# 1.net
KiCad netlist of a schematic drawn in Altium Designer
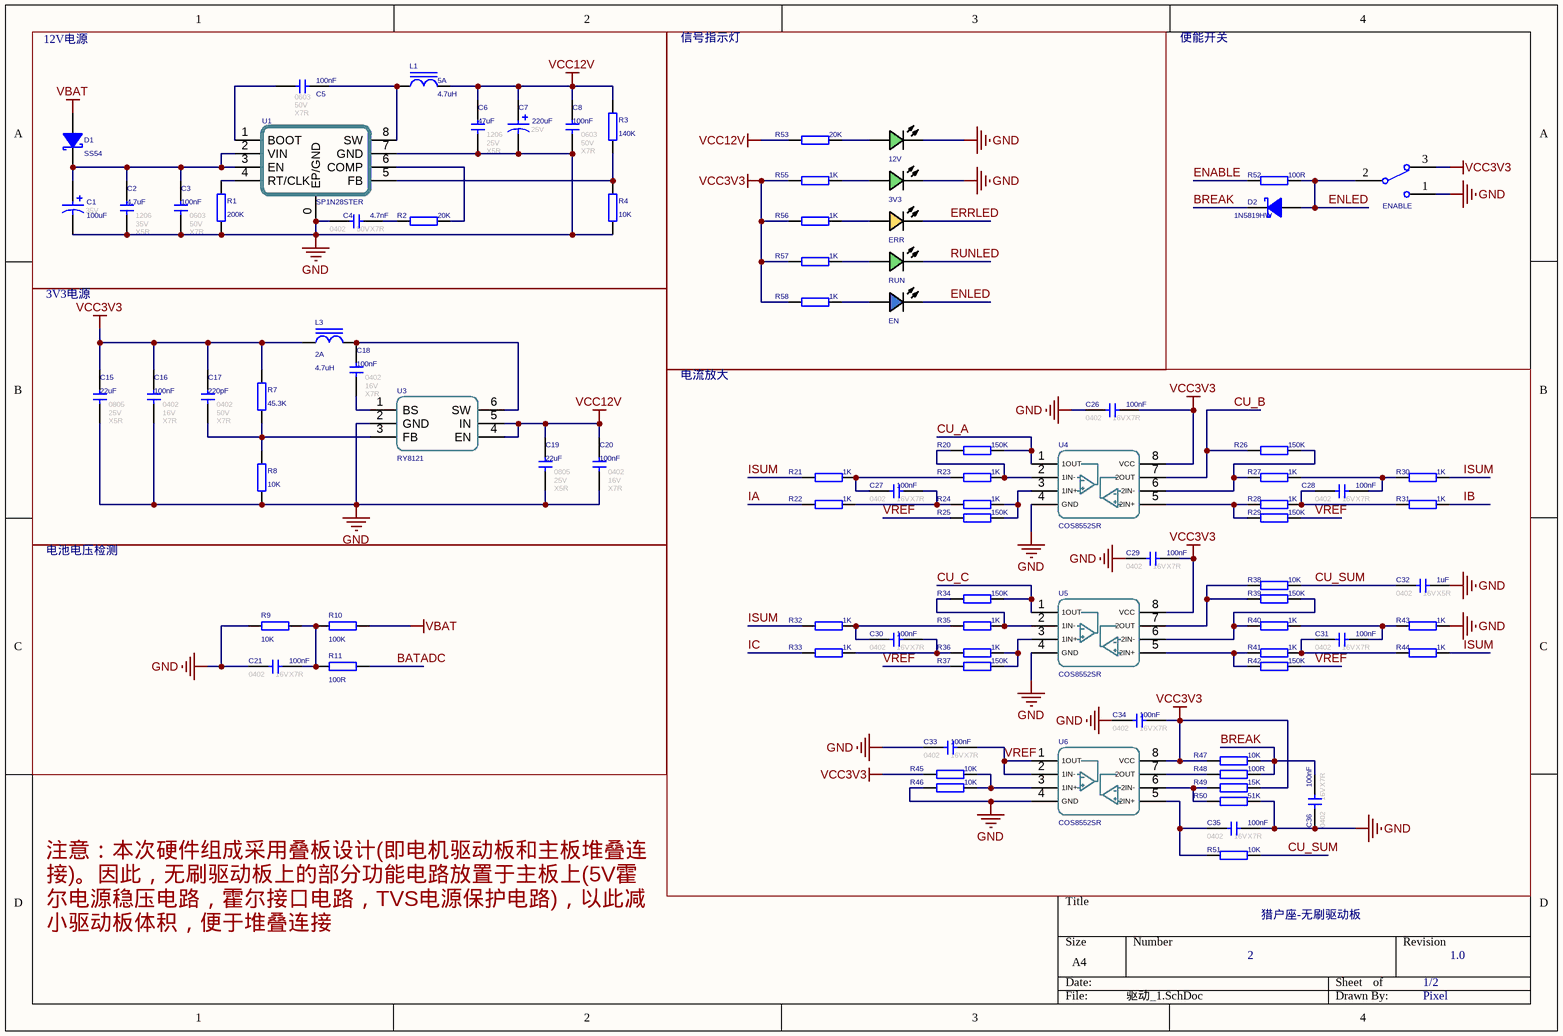
[diagram p0: 驱动_1.SchDoc]

(export (version "E")
  (design (tool "Eeschema 10.0.6"))
  (components
    (comp (ref "3V3")
      (value "翠绿贴片LED")
      (footprint "LEDC1608(0603)-L")
      (fields (field (name "PUBLISHER") "Altium Limited"))
      (libsource (lib "无刷驱动-Infineon-AUIRS2181S-GTM-6S") (part "LED Chip Green"))
    )
    (comp (ref "12V")
      (value "翠绿贴片LED")
      (footprint "LEDC1608(0603)-L")
      (fields (field (name "PUBLISHER") "Altium Limited"))
      (libsource (lib "无刷驱动-Infineon-AUIRS2181S-GTM-6S") (part "LED Chip Green"))
    )
    (comp (ref "C1")
      (value "100uF")
      (footprint "CAP-E-S 6.3")
      (description "贴片电解电容 100uF 35V 6.3x7.7")
      (fields (field (name "VOLTAGE") "35V") (field (name "Comment") "100uF 35V 铝电解"))
      (libsource (lib "无刷驱动-Infineon-AUIRS2181S-GTM-6S") (part "E-S 100uF 35V 6.3x7.7"))
    )
    (comp (ref "C2")
      (value "4.7uF")
      (footprint "1206")
      (description "贴片瓷片电容; MLCC; 1206(3216);")
      (fields
        (field (name "VOLTAGE") "35V")
        (field (name "TYPE") "X5R")
        (field (name "Comment") "4.7uF 35V X5R")
      )
      (libsource (lib "无刷驱动-Infineon-AUIRS2181S-GTM-6S") (part "4.7uF 1206 35V X5R"))
    )
    (comp (ref "C3")
      (value "100nF")
      (footprint "0603")
      (description "贴片瓷片电容; MLCC; 0603(1608);")
      (fields
        (field (name "VOLTAGE") "50V")
        (field (name "TYPE") "X7R")
        (field (name "Comment") "100nF 50V X7R")
      )
      (libsource (lib "无刷驱动-Infineon-AUIRS2181S-GTM-6S") (part "100nF 0603 50V X7R"))
    )
    (comp (ref "C4")
      (value "4.7nF")
      (footprint "0402")
      (description "贴片瓷片电容; MLCC; 0402(1005);")
      (fields
        (field (name "VOLTAGE") "50V")
        (field (name "TYPE") "X7R")
        (field (name "Comment") "4.7nF 50V X7R")
      )
      (libsource (lib "无刷驱动-Infineon-AUIRS2181S-GTM-6S") (part "4.7nF 0402 50V X7R"))
    )
    (comp (ref "C5")
      (value "100nF")
      (footprint "0603")
      (description "贴片瓷片电容; MLCC; 0603(1608);")
      (fields
        (field (name "VOLTAGE") "50V")
        (field (name "TYPE") "X7R")
        (field (name "Comment") "100nF 50V X7R")
      )
      (libsource (lib "无刷驱动-Infineon-AUIRS2181S-GTM-6S") (part "100nF 0603 50V X7R"))
    )
    (comp (ref "C6")
      (value "47uF")
      (footprint "1206")
      (description "贴片瓷片电容; MLCC; 1206(3216);")
      (fields
        (field (name "VOLTAGE") "25V")
        (field (name "TYPE") "X5R")
        (field (name "Comment") "47uF 25V X5R")
      )
      (libsource (lib "无刷驱动-Infineon-AUIRS2181S-GTM-6S") (part "47uF 1206 25V X5R"))
    )
    (comp (ref "C7")
      (value "220uF")
      (footprint "CAP-E-S 6.3")
      (description "贴片电解电容 220uF 25V 6.3x7.7")
      (fields (field (name "VOLTAGE") "25V") (field (name "Comment") "220uF 25V 铝电解"))
      (libsource (lib "无刷驱动-Infineon-AUIRS2181S-GTM-6S") (part "E-S 220uF 25V 6.3x7.7"))
    )
    (comp (ref "C8")
      (value "100nF")
      (footprint "0603")
      (description "贴片瓷片电容; MLCC; 0603(1608);")
      (fields
        (field (name "VOLTAGE") "50V")
        (field (name "TYPE") "X7R")
        (field (name "Comment") "100nF 50V X7R")
      )
      (libsource (lib "无刷驱动-Infineon-AUIRS2181S-GTM-6S") (part "100nF 0603 50V X7R"))
    )
    (comp (ref "C15")
      (value "22uF")
      (footprint "0805")
      (description "贴片瓷片电容; MLCC; 0805(2012);")
      (fields
        (field (name "VOLTAGE") "25V")
        (field (name "TYPE") "X5R")
        (field (name "Comment") "22uF 25V X5R")
      )
      (libsource (lib "无刷驱动-Infineon-AUIRS2181S-GTM-6S") (part "22uF 0805 25V X5R"))
    )
    (comp (ref "C16")
      (value "100nF")
      (footprint "0402")
      (description "贴片瓷片电容; MLCC; 0402(1005);")
      (fields
        (field (name "VOLTAGE") "16V")
        (field (name "TYPE") "X7R")
        (field (name "Comment") "100nF 16V X7R")
      )
      (libsource (lib "无刷驱动-Infineon-AUIRS2181S-GTM-6S") (part "100nF 0402 16V X7R"))
    )
    (comp (ref "C17")
      (value "220pF")
      (footprint "0402")
      (description "贴片瓷片电容; MLCC; 0402(1005);")
      (fields
        (field (name "VOLTAGE") "50V")
        (field (name "TYPE") "X7R")
        (field (name "Comment") "220pF 50V X7R")
      )
      (libsource (lib "无刷驱动-Infineon-AUIRS2181S-GTM-6S") (part "220pF 0402 50V X7R"))
    )
    (comp (ref "C18")
      (value "100nF")
      (footprint "0402")
      (description "贴片瓷片电容; MLCC; 0402(1005);")
      (fields
        (field (name "VOLTAGE") "16V")
        (field (name "TYPE") "X7R")
        (field (name "Comment") "100nF 16V X7R")
      )
      (libsource (lib "无刷驱动-Infineon-AUIRS2181S-GTM-6S") (part "100nF 0402 16V X7R"))
    )
    (comp (ref "C19")
      (value "22uF")
      (footprint "0805")
      (description "贴片瓷片电容; MLCC; 0805(2012);")
      (fields
        (field (name "VOLTAGE") "25V")
        (field (name "TYPE") "X5R")
        (field (name "Comment") "22uF 25V X5R")
      )
      (libsource (lib "无刷驱动-Infineon-AUIRS2181S-GTM-6S") (part "22uF 0805 25V X5R"))
    )
    (comp (ref "C20")
      (value "100nF")
      (footprint "0402")
      (description "贴片瓷片电容; MLCC; 0402(1005);")
      (fields
        (field (name "VOLTAGE") "16V")
        (field (name "TYPE") "X7R")
        (field (name "Comment") "100nF 16V X7R")
      )
      (libsource (lib "无刷驱动-Infineon-AUIRS2181S-GTM-6S") (part "100nF 0402 16V X7R"))
    )
    (comp (ref "C21")
      (value "100nF")
      (footprint "0402")
      (description "贴片瓷片电容; MLCC; 0402(1005);")
      (fields
        (field (name "VOLTAGE") "16V")
        (field (name "TYPE") "X7R")
        (field (name "Comment") "100nF 16V X7R")
      )
      (libsource (lib "无刷驱动-Infineon-AUIRS2181S-GTM-6S") (part "100nF 0402 16V X7R"))
    )
    (comp (ref "C26")
      (value "100nF")
      (footprint "0402")
      (description "贴片瓷片电容; MLCC; 0402(1005);")
      (fields
        (field (name "VOLTAGE") "16V")
        (field (name "TYPE") "X7R")
        (field (name "Comment") "100nF 16V X7R")
      )
      (libsource (lib "无刷驱动-Infineon-AUIRS2181S-GTM-6S") (part "100nF 0402 16V X7R"))
    )
    (comp (ref "C27")
      (value "100nF")
      (footprint "0402")
      (description "贴片瓷片电容; MLCC; 0402(1005);")
      (fields
        (field (name "VOLTAGE") "16V")
        (field (name "TYPE") "X7R")
        (field (name "Comment") "100nF 16V X7R")
      )
      (libsource (lib "无刷驱动-Infineon-AUIRS2181S-GTM-6S") (part "100nF 0402 16V X7R"))
    )
    (comp (ref "C28")
      (value "100nF")
      (footprint "0402")
      (description "贴片瓷片电容; MLCC; 0402(1005);")
      (fields
        (field (name "VOLTAGE") "16V")
        (field (name "TYPE") "X7R")
        (field (name "Comment") "100nF 16V X7R")
      )
      (libsource (lib "无刷驱动-Infineon-AUIRS2181S-GTM-6S") (part "100nF 0402 16V X7R"))
    )
    (comp (ref "C29")
      (value "100nF")
      (footprint "0402")
      (description "贴片瓷片电容; MLCC; 0402(1005);")
      (fields
        (field (name "VOLTAGE") "16V")
        (field (name "TYPE") "X7R")
        (field (name "Comment") "100nF 16V X7R")
      )
      (libsource (lib "无刷驱动-Infineon-AUIRS2181S-GTM-6S") (part "100nF 0402 16V X7R"))
    )
    (comp (ref "C30")
      (value "100nF")
      (footprint "0402")
      (description "贴片瓷片电容; MLCC; 0402(1005);")
      (fields
        (field (name "VOLTAGE") "16V")
        (field (name "TYPE") "X7R")
        (field (name "Comment") "100nF 16V X7R")
      )
      (libsource (lib "无刷驱动-Infineon-AUIRS2181S-GTM-6S") (part "100nF 0402 16V X7R"))
    )
    (comp (ref "C31")
      (value "100nF")
      (footprint "0402")
      (description "贴片瓷片电容; MLCC; 0402(1005);")
      (fields
        (field (name "VOLTAGE") "16V")
        (field (name "TYPE") "X7R")
        (field (name "Comment") "100nF 16V X7R")
      )
      (libsource (lib "无刷驱动-Infineon-AUIRS2181S-GTM-6S") (part "100nF 0402 16V X7R"))
    )
    (comp (ref "C32")
      (value "1uF")
      (footprint "0402")
      (description "贴片瓷片电容; MLCC; 0402(1005);")
      (fields
        (field (name "VOLTAGE") "16V")
        (field (name "TYPE") "X5R")
        (field (name "Comment") "1uF 16V X5R")
      )
      (libsource (lib "无刷驱动-Infineon-AUIRS2181S-GTM-6S") (part "1uF 0402 16V X5R"))
    )
    (comp (ref "C33")
      (value "100nF")
      (footprint "0402")
      (description "贴片瓷片电容; MLCC; 0402(1005);")
      (fields
        (field (name "VOLTAGE") "16V")
        (field (name "TYPE") "X7R")
        (field (name "Comment") "100nF 16V X7R")
      )
      (libsource (lib "无刷驱动-Infineon-AUIRS2181S-GTM-6S") (part "100nF 0402 16V X7R"))
    )
    (comp (ref "C34")
      (value "100nF")
      (footprint "0402")
      (description "贴片瓷片电容; MLCC; 0402(1005);")
      (fields
        (field (name "VOLTAGE") "16V")
        (field (name "TYPE") "X7R")
        (field (name "Comment") "100nF 16V X7R")
      )
      (libsource (lib "无刷驱动-Infineon-AUIRS2181S-GTM-6S") (part "100nF 0402 16V X7R"))
    )
    (comp (ref "C35")
      (value "100nF")
      (footprint "0402")
      (description "贴片瓷片电容; MLCC; 0402(1005);")
      (fields
        (field (name "VOLTAGE") "16V")
        (field (name "TYPE") "X7R")
        (field (name "Comment") "100nF 16V X7R")
      )
      (libsource (lib "无刷驱动-Infineon-AUIRS2181S-GTM-6S") (part "100nF 0402 16V X7R"))
    )
    (comp (ref "C36")
      (value "100nF")
      (footprint "0402")
      (description "贴片瓷片电容; MLCC; 0402(1005);")
      (fields
        (field (name "VOLTAGE") "16V")
        (field (name "TYPE") "X7R")
        (field (name "Comment") "100nF 16V X7R")
      )
      (libsource (lib "无刷驱动-Infineon-AUIRS2181S-GTM-6S") (part "100nF 0402 16V X7R"))
    )
    (comp (ref "D1")
      (value "SS54")
      (footprint "SMA-L[DO-214AC]")
      (description "SS54 肖特基二极管")
      (libsource (lib "无刷驱动-Infineon-AUIRS2181S-GTM-6S") (part "SS54"))
    )
    (comp (ref "D2")
      (value "1N5819HW")
      (footprint "SOD-123-L")
      (description "1N5819HW 肖特基二极管")
      (libsource (lib "无刷驱动-Infineon-AUIRS2181S-GTM-6S") (part "1N5819HW"))
    )
    (comp (ref "EN")
      (value "蓝色贴片LED")
      (footprint "LEDC1608(0603)-L")
      (fields (field (name "PUBLISHER") "Altium Limited"))
      (libsource (lib "无刷驱动-Infineon-AUIRS2181S-GTM-6S") (part "LED Chip Blue"))
    )
    (comp (ref "ENABLE")
      (value "SW-SPDT")
      (footprint "SS12D10")
      (description "单刀双掷开关 3脚船型、钮子、拨动开关 SPDT Subminiature Toggle Switch")
      (fields (field (name "PUBLISHER") "Altium Limited"))
      (libsource (lib "无刷驱动-Infineon-AUIRS2181S-GTM-6S") (part "SW-SPDT"))
    )
    (comp (ref "ERR")
      (value "黄色贴片LED")
      (footprint "LEDC1608(0603)-L")
      (fields (field (name "PUBLISHER") "Altium Limited"))
      (libsource (lib "无刷驱动-Infineon-AUIRS2181S-GTM-6S") (part "LED Chip Yellow"))
    )
    (comp (ref "L1")
      (value "4.7uH")
      (footprint "SLO2520")
      (description "功率电感")
      (fields
        (field (name "IMAX") "5A")
        (field (name "Comment") "4.7uH 5A")
        (field (name "PUBLISHER") "Altium Limited")
      )
      (libsource (lib "无刷驱动-Infineon-AUIRS2181S-GTM-6S") (part "Ind-Power"))
    )
    (comp (ref "L3")
      (value "4.7uH")
      (footprint "SLO2520")
      (description "功率电感")
      (fields
        (field (name "IMAX") "2A")
        (field (name "Comment") "4.7uH 2A")
        (field (name "PUBLISHER") "Altium Limited")
      )
      (libsource (lib "无刷驱动-Infineon-AUIRS2181S-GTM-6S") (part "Ind-Power"))
    )
    (comp (ref "R1")
      (value "200K")
      (footprint "RESC1005[0402]S-N")
      (description "贴片电阻")
      (fields (field (name "POWER") "1/8W") (field (name "TOLERANCE") "±1%"))
      (libsource (lib "无刷驱动-Infineon-AUIRS2181S-GTM-6S") (part "Res-Chip_10"))
    )
    (comp (ref "R2")
      (value "20K")
      (footprint "RESC1005[0402]S-N")
      (description "贴片电阻")
      (fields (field (name "POWER") "1/8W") (field (name "TOLERANCE") "±1%"))
      (libsource (lib "无刷驱动-Infineon-AUIRS2181S-GTM-6S") (part "Res-Chip_7"))
    )
    (comp (ref "R3")
      (value "140K")
      (footprint "RESC1005[0402]S-N")
      (description "贴片电阻")
      (fields (field (name "POWER") "1/8W") (field (name "TOLERANCE") "±1%"))
      (libsource (lib "无刷驱动-Infineon-AUIRS2181S-GTM-6S") (part "Res-Chip_11"))
    )
    (comp (ref "R4")
      (value "10K")
      (footprint "RESC1005[0402]S-N")
      (description "贴片电阻")
      (fields (field (name "POWER") "1/8W") (field (name "TOLERANCE") "±1%"))
      (libsource (lib "无刷驱动-Infineon-AUIRS2181S-GTM-6S") (part "Res-Chip_1"))
    )
    (comp (ref "R7")
      (value "45.3K")
      (footprint "RESC1005[0402]S-N")
      (description "贴片电阻")
      (fields (field (name "POWER") "1/8W") (field (name "TOLERANCE") "±1%"))
      (libsource (lib "无刷驱动-Infineon-AUIRS2181S-GTM-6S") (part "Res-Chip_12"))
    )
    (comp (ref "R8")
      (value "10K")
      (footprint "RESC1005[0402]S-N")
      (description "贴片电阻")
      (fields (field (name "POWER") "1/8W") (field (name "TOLERANCE") "±1%"))
      (libsource (lib "无刷驱动-Infineon-AUIRS2181S-GTM-6S") (part "Res-Chip_1"))
    )
    (comp (ref "R9")
      (value "10K")
      (footprint "RESC1005[0402]S-N")
      (description "贴片电阻")
      (fields (field (name "POWER") "1/8W") (field (name "TOLERANCE") "±1%"))
      (libsource (lib "无刷驱动-Infineon-AUIRS2181S-GTM-6S") (part "Res-Chip_1"))
    )
    (comp (ref "R10")
      (value "100K")
      (footprint "RESC1005[0402]S-N")
      (description "贴片电阻")
      (fields (field (name "POWER") "1/8W") (field (name "TOLERANCE") "±1%"))
      (libsource (lib "无刷驱动-Infineon-AUIRS2181S-GTM-6S") (part "Res-Chip_9"))
    )
    (comp (ref "R11")
      (value "100R")
      (footprint "RESC1005[0402]S-N")
      (description "贴片电阻")
      (fields (field (name "POWER") "1/8W") (field (name "TOLERANCE") "±1%"))
      (libsource (lib "无刷驱动-Infineon-AUIRS2181S-GTM-6S") (part "Res-Chip_5"))
    )
    (comp (ref "R20")
      (value "150K")
      (footprint "RESC1005[0402]S-N")
      (description "贴片电阻")
      (fields (field (name "POWER") "1/8W") (field (name "TOLERANCE") "±1%"))
      (libsource (lib "无刷驱动-Infineon-AUIRS2181S-GTM-6S") (part "Res-Chip_13"))
    )
    (comp (ref "R21")
      (value "1K")
      (footprint "RESC1005[0402]S-N")
      (description "贴片电阻")
      (fields (field (name "POWER") "1/8W") (field (name "TOLERANCE") "±1%"))
      (libsource (lib "无刷驱动-Infineon-AUIRS2181S-GTM-6S") (part "Res-Chip_6"))
    )
    (comp (ref "R22")
      (value "1K")
      (footprint "RESC1005[0402]S-N")
      (description "贴片电阻")
      (fields (field (name "POWER") "1/8W") (field (name "TOLERANCE") "±1%"))
      (libsource (lib "无刷驱动-Infineon-AUIRS2181S-GTM-6S") (part "Res-Chip_6"))
    )
    (comp (ref "R23")
      (value "1K")
      (footprint "RESC1005[0402]S-N")
      (description "贴片电阻")
      (fields (field (name "POWER") "1/8W") (field (name "TOLERANCE") "±1%"))
      (libsource (lib "无刷驱动-Infineon-AUIRS2181S-GTM-6S") (part "Res-Chip_6"))
    )
    (comp (ref "R24")
      (value "1K")
      (footprint "RESC1005[0402]S-N")
      (description "贴片电阻")
      (fields (field (name "POWER") "1/8W") (field (name "TOLERANCE") "±1%"))
      (libsource (lib "无刷驱动-Infineon-AUIRS2181S-GTM-6S") (part "Res-Chip_6"))
    )
    (comp (ref "R25")
      (value "150K")
      (footprint "RESC1005[0402]S-N")
      (description "贴片电阻")
      (fields (field (name "POWER") "1/8W") (field (name "TOLERANCE") "±1%"))
      (libsource (lib "无刷驱动-Infineon-AUIRS2181S-GTM-6S") (part "Res-Chip_13"))
    )
    (comp (ref "R26")
      (value "150K")
      (footprint "RESC1005[0402]S-N")
      (description "贴片电阻")
      (fields (field (name "POWER") "1/8W") (field (name "TOLERANCE") "±1%"))
      (libsource (lib "无刷驱动-Infineon-AUIRS2181S-GTM-6S") (part "Res-Chip_13"))
    )
    (comp (ref "R27")
      (value "1K")
      (footprint "RESC1005[0402]S-N")
      (description "贴片电阻")
      (fields (field (name "POWER") "1/8W") (field (name "TOLERANCE") "±1%"))
      (libsource (lib "无刷驱动-Infineon-AUIRS2181S-GTM-6S") (part "Res-Chip_6"))
    )
    (comp (ref "R28")
      (value "1K")
      (footprint "RESC1005[0402]S-N")
      (description "贴片电阻")
      (fields (field (name "POWER") "1/8W") (field (name "TOLERANCE") "±1%"))
      (libsource (lib "无刷驱动-Infineon-AUIRS2181S-GTM-6S") (part "Res-Chip_6"))
    )
    (comp (ref "R29")
      (value "150K")
      (footprint "RESC1005[0402]S-N")
      (description "贴片电阻")
      (fields (field (name "POWER") "1/8W") (field (name "TOLERANCE") "±1%"))
      (libsource (lib "无刷驱动-Infineon-AUIRS2181S-GTM-6S") (part "Res-Chip_13"))
    )
    (comp (ref "R30")
      (value "1K")
      (footprint "RESC1005[0402]S-N")
      (description "贴片电阻")
      (fields (field (name "POWER") "1/8W") (field (name "TOLERANCE") "±1%"))
      (libsource (lib "无刷驱动-Infineon-AUIRS2181S-GTM-6S") (part "Res-Chip_6"))
    )
    (comp (ref "R31")
      (value "1K")
      (footprint "RESC1005[0402]S-N")
      (description "贴片电阻")
      (fields (field (name "POWER") "1/8W") (field (name "TOLERANCE") "±1%"))
      (libsource (lib "无刷驱动-Infineon-AUIRS2181S-GTM-6S") (part "Res-Chip_6"))
    )
    (comp (ref "R32")
      (value "1K")
      (footprint "RESC1005[0402]S-N")
      (description "贴片电阻")
      (fields (field (name "POWER") "1/8W") (field (name "TOLERANCE") "±1%"))
      (libsource (lib "无刷驱动-Infineon-AUIRS2181S-GTM-6S") (part "Res-Chip_6"))
    )
    (comp (ref "R33")
      (value "1K")
      (footprint "RESC1005[0402]S-N")
      (description "贴片电阻")
      (fields (field (name "POWER") "1/8W") (field (name "TOLERANCE") "±1%"))
      (libsource (lib "无刷驱动-Infineon-AUIRS2181S-GTM-6S") (part "Res-Chip_6"))
    )
    (comp (ref "R34")
      (value "150K")
      (footprint "RESC1005[0402]S-N")
      (description "贴片电阻")
      (fields (field (name "POWER") "1/8W") (field (name "TOLERANCE") "±1%"))
      (libsource (lib "无刷驱动-Infineon-AUIRS2181S-GTM-6S") (part "Res-Chip_13"))
    )
    (comp (ref "R35")
      (value "1K")
      (footprint "RESC1005[0402]S-N")
      (description "贴片电阻")
      (fields (field (name "POWER") "1/8W") (field (name "TOLERANCE") "±1%"))
      (libsource (lib "无刷驱动-Infineon-AUIRS2181S-GTM-6S") (part "Res-Chip_6"))
    )
    (comp (ref "R36")
      (value "1K")
      (footprint "RESC1005[0402]S-N")
      (description "贴片电阻")
      (fields (field (name "POWER") "1/8W") (field (name "TOLERANCE") "±1%"))
      (libsource (lib "无刷驱动-Infineon-AUIRS2181S-GTM-6S") (part "Res-Chip_6"))
    )
    (comp (ref "R37")
      (value "150K")
      (footprint "RESC1005[0402]S-N")
      (description "贴片电阻")
      (fields (field (name "POWER") "1/8W") (field (name "TOLERANCE") "±1%"))
      (libsource (lib "无刷驱动-Infineon-AUIRS2181S-GTM-6S") (part "Res-Chip_13"))
    )
    (comp (ref "R38")
      (value "10K")
      (footprint "RESC1005[0402]S-N")
      (description "贴片电阻")
      (fields (field (name "POWER") "1/8W") (field (name "TOLERANCE") "±1%"))
      (libsource (lib "无刷驱动-Infineon-AUIRS2181S-GTM-6S") (part "Res-Chip_1"))
    )
    (comp (ref "R39")
      (value "150K")
      (footprint "RESC1005[0402]S-N")
      (description "贴片电阻")
      (fields (field (name "POWER") "1/8W") (field (name "TOLERANCE") "±1%"))
      (libsource (lib "无刷驱动-Infineon-AUIRS2181S-GTM-6S") (part "Res-Chip_13"))
    )
    (comp (ref "R40")
      (value "1K")
      (footprint "RESC1005[0402]S-N")
      (description "贴片电阻")
      (fields (field (name "POWER") "1/8W") (field (name "TOLERANCE") "±1%"))
      (libsource (lib "无刷驱动-Infineon-AUIRS2181S-GTM-6S") (part "Res-Chip_6"))
    )
    (comp (ref "R41")
      (value "1K")
      (footprint "RESC1005[0402]S-N")
      (description "贴片电阻")
      (fields (field (name "POWER") "1/8W") (field (name "TOLERANCE") "±1%"))
      (libsource (lib "无刷驱动-Infineon-AUIRS2181S-GTM-6S") (part "Res-Chip_6"))
    )
    (comp (ref "R42")
      (value "150K")
      (footprint "RESC1005[0402]S-N")
      (description "贴片电阻")
      (fields (field (name "POWER") "1/8W") (field (name "TOLERANCE") "±1%"))
      (libsource (lib "无刷驱动-Infineon-AUIRS2181S-GTM-6S") (part "Res-Chip_13"))
    )
    (comp (ref "R43")
      (value "1K")
      (footprint "RESC1005[0402]S-N")
      (description "贴片电阻")
      (fields (field (name "POWER") "1/8W") (field (name "TOLERANCE") "±1%"))
      (libsource (lib "无刷驱动-Infineon-AUIRS2181S-GTM-6S") (part "Res-Chip_6"))
    )
    (comp (ref "R44")
      (value "1K")
      (footprint "RESC1005[0402]S-N")
      (description "贴片电阻")
      (fields (field (name "POWER") "1/8W") (field (name "TOLERANCE") "±1%"))
      (libsource (lib "无刷驱动-Infineon-AUIRS2181S-GTM-6S") (part "Res-Chip_6"))
    )
    (comp (ref "R45")
      (value "10K")
      (footprint "RESC1005[0402]S-N")
      (description "贴片电阻")
      (fields (field (name "POWER") "1/8W") (field (name "TOLERANCE") "±1%"))
      (libsource (lib "无刷驱动-Infineon-AUIRS2181S-GTM-6S") (part "Res-Chip_1"))
    )
    (comp (ref "R46")
      (value "10K")
      (footprint "RESC1005[0402]S-N")
      (description "贴片电阻")
      (fields (field (name "POWER") "1/8W") (field (name "TOLERANCE") "±1%"))
      (libsource (lib "无刷驱动-Infineon-AUIRS2181S-GTM-6S") (part "Res-Chip_1"))
    )
    (comp (ref "R47")
      (value "10K")
      (footprint "RESC1005[0402]S-N")
      (description "贴片电阻")
      (fields (field (name "POWER") "1/8W") (field (name "TOLERANCE") "±1%"))
      (libsource (lib "无刷驱动-Infineon-AUIRS2181S-GTM-6S") (part "Res-Chip_1"))
    )
    (comp (ref "R48")
      (value "100R")
      (footprint "RESC1005[0402]S-N")
      (description "贴片电阻")
      (fields (field (name "POWER") "1/8W") (field (name "TOLERANCE") "±1%"))
      (libsource (lib "无刷驱动-Infineon-AUIRS2181S-GTM-6S") (part "Res-Chip_5"))
    )
    (comp (ref "R49")
      (value "15K")
      (footprint "RESC1005[0402]S-N")
      (description "贴片电阻")
      (fields (field (name "POWER") "1/8W") (field (name "TOLERANCE") "±1%"))
      (libsource (lib "无刷驱动-Infineon-AUIRS2181S-GTM-6S") (part "Res-Chip_15"))
    )
    (comp (ref "R50")
      (value "51K")
      (footprint "RESC1005[0402]S-N")
      (description "贴片电阻")
      (fields (field (name "POWER") "1/8W") (field (name "TOLERANCE") "±1%"))
      (libsource (lib "无刷驱动-Infineon-AUIRS2181S-GTM-6S") (part "Res-Chip_14"))
    )
    (comp (ref "R51")
      (value "10K")
      (footprint "RESC1005[0402]S-N")
      (description "贴片电阻")
      (fields (field (name "POWER") "1/8W") (field (name "TOLERANCE") "±1%"))
      (libsource (lib "无刷驱动-Infineon-AUIRS2181S-GTM-6S") (part "Res-Chip_1"))
    )
    (comp (ref "R52")
      (value "100R")
      (footprint "RESC1005[0402]S-N")
      (description "贴片电阻")
      (fields (field (name "POWER") "1/8W") (field (name "TOLERANCE") "±1%"))
      (libsource (lib "无刷驱动-Infineon-AUIRS2181S-GTM-6S") (part "Res-Chip_5"))
    )
    (comp (ref "R53")
      (value "20K")
      (footprint "RESC1005[0402]S-N")
      (description "贴片电阻")
      (fields (field (name "POWER") "1/8W") (field (name "TOLERANCE") "±1%"))
      (libsource (lib "无刷驱动-Infineon-AUIRS2181S-GTM-6S") (part "Res-Chip_7"))
    )
    (comp (ref "R55")
      (value "1K")
      (footprint "RESC1005[0402]S-N")
      (description "贴片电阻")
      (fields (field (name "POWER") "1/8W") (field (name "TOLERANCE") "±1%"))
      (libsource (lib "无刷驱动-Infineon-AUIRS2181S-GTM-6S") (part "Res-Chip_6"))
    )
    (comp (ref "R56")
      (value "1K")
      (footprint "RESC1005[0402]S-N")
      (description "贴片电阻")
      (fields (field (name "POWER") "1/8W") (field (name "TOLERANCE") "±1%"))
      (libsource (lib "无刷驱动-Infineon-AUIRS2181S-GTM-6S") (part "Res-Chip_6"))
    )
    (comp (ref "R57")
      (value "1K")
      (footprint "RESC1005[0402]S-N")
      (description "贴片电阻")
      (fields (field (name "POWER") "1/8W") (field (name "TOLERANCE") "±1%"))
      (libsource (lib "无刷驱动-Infineon-AUIRS2181S-GTM-6S") (part "Res-Chip_6"))
    )
    (comp (ref "R58")
      (value "1K")
      (footprint "RESC1005[0402]S-N")
      (description "贴片电阻")
      (fields (field (name "POWER") "1/8W") (field (name "TOLERANCE") "±1%"))
      (libsource (lib "无刷驱动-Infineon-AUIRS2181S-GTM-6S") (part "Res-Chip_6"))
    )
    (comp (ref "RUN")
      (value "翠绿贴片LED")
      (footprint "LEDC1608(0603)-L")
      (fields (field (name "PUBLISHER") "Altium Limited"))
      (libsource (lib "无刷驱动-Infineon-AUIRS2181S-GTM-6S") (part "LED Chip Green"))
    )
    (comp (ref "U1")
      (value "SP1N28STER")
      (footprint "SOP-8E")
      (libsource (lib "无刷驱动-Infineon-AUIRS2181S-GTM-6S") (part "SP1N28STER"))
    )
    (comp (ref "U3")
      (value "RY8121")
      (footprint "SOT-23-6")
      (description "18V 2A 1MHz Synchronous Step-Down Regulator")
      (libsource (lib "无刷驱动-Infineon-AUIRS2181S-GTM-6S") (part "RY8121"))
    )
    (comp (ref "U4")
      (value "COS8552SR")
      (footprint "SOP-8")
      (description "COS8552SR 二路通用运算放大器")
      (libsource (lib "无刷驱动-Infineon-AUIRS2181S-GTM-6S") (part "COS8552SR"))
    )
    (comp (ref "U5")
      (value "COS8552SR")
      (footprint "SOP-8")
      (description "COS8552SR 二路通用运算放大器")
      (libsource (lib "无刷驱动-Infineon-AUIRS2181S-GTM-6S") (part "COS8552SR"))
    )
    (comp (ref "U6")
      (value "COS8552SR")
      (footprint "SOP-8")
      (description "COS8552SR 二路通用运算放大器")
      (libsource (lib "无刷驱动-Infineon-AUIRS2181S-GTM-6S") (part "COS8552SR"))
    )
  )
  (nets
    (net (code "1") (name "/BATADC") (class "Default")
      (node (ref "R11") (pin "2") (pinfunction "2_2") (pintype "passive"))
    )
    (net (code "2") (name "/BREAK") (class "Default")
      (node (ref "C36") (pin "2") (pinfunction "2_2") (pintype "passive"))
      (node (ref "D2") (pin "K") (pinfunction "K_K") (pintype "passive"))
      (node (ref "R47") (pin "2") (pinfunction "2_2") (pintype "passive"))
      (node (ref "R48") (pin "2") (pinfunction "2_2") (pintype "passive"))
    )
    (net (code "3") (name "/CU_A") (class "Default")
      (node (ref "R20") (pin "2") (pinfunction "2_2") (pintype "passive"))
      (node (ref "U4") (pin "1") (pinfunction "1OUT_1") (pintype "passive"))
    )
    (net (code "4") (name "/CU_B") (class "Default")
      (node (ref "R26") (pin "2") (pinfunction "2_2") (pintype "passive"))
      (node (ref "U4") (pin "7") (pinfunction "2OUT_7") (pintype "passive"))
    )
    (net (code "5") (name "/CU_C") (class "Default")
      (node (ref "R34") (pin "2") (pinfunction "2_2") (pintype "passive"))
      (node (ref "U5") (pin "1") (pinfunction "1OUT_1") (pintype "passive"))
    )
    (net (code "6") (name "/CU_SUM") (class "Default")
      (node (ref "C32") (pin "1") (pinfunction "1_1") (pintype "passive"))
      (node (ref "R38") (pin "2") (pinfunction "2_2") (pintype "passive"))
      (node (ref "R51") (pin "2") (pinfunction "2_2") (pintype "passive"))
    )
    (net (code "7") (name "/ENABLE") (class "Default")
      (node (ref "R52") (pin "1") (pinfunction "1_1") (pintype "passive"))
    )
    (net (code "8") (name "/ENLED") (class "Default")
      (node (ref "D2") (pin "A") (pinfunction "A_A") (pintype "passive"))
      (node (ref "EN") (pin "C") (pinfunction "C_C") (pintype "passive"))
      (node (ref "ENABLE") (pin "2") (pintype "passive"))
      (node (ref "R52") (pin "2") (pinfunction "2_2") (pintype "passive"))
    )
    (net (code "9") (name "/ERRLED") (class "Default")
      (node (ref "ERR") (pin "C") (pinfunction "C_C") (pintype "passive"))
    )
    (net (code "10") (name "/IA") (class "Default")
      (node (ref "R22") (pin "1") (pinfunction "1_1") (pintype "passive"))
    )
    (net (code "11") (name "/IB") (class "Default")
      (node (ref "R31") (pin "1") (pinfunction "1_1") (pintype "passive"))
    )
    (net (code "12") (name "/IC") (class "Default")
      (node (ref "R33") (pin "1") (pinfunction "1_1") (pintype "passive"))
    )
    (net (code "13") (name "/ISUM") (class "Default")
      (node (ref "R21") (pin "1") (pinfunction "1_1") (pintype "passive"))
      (node (ref "R30") (pin "1") (pinfunction "1_1") (pintype "passive"))
      (node (ref "R32") (pin "1") (pinfunction "1_1") (pintype "passive"))
      (node (ref "R44") (pin "1") (pinfunction "1_1") (pintype "passive"))
    )
    (net (code "14") (name "/RUNLED") (class "Default")
      (node (ref "RUN") (pin "C") (pinfunction "C_C") (pintype "passive"))
    )
    (net (code "15") (name "/VREF") (class "Default")
      (node (ref "C33") (pin "2") (pinfunction "2_2") (pintype "passive"))
      (node (ref "R25") (pin "1") (pinfunction "1_1") (pintype "passive"))
      (node (ref "R29") (pin "1") (pinfunction "1_1") (pintype "passive"))
      (node (ref "R37") (pin "1") (pinfunction "1_1") (pintype "passive"))
      (node (ref "R42") (pin "1") (pinfunction "1_1") (pintype "passive"))
      (node (ref "U6") (pin "1") (pinfunction "1OUT_1") (pintype "passive"))
      (node (ref "U6") (pin "2") (pinfunction "1IN-_2") (pintype "passive"))
    )
    (net (code "16") (name "GND") (class "Default")
      (node (ref "12V") (pin "C") (pinfunction "C_C") (pintype "passive"))
      (node (ref "3V3") (pin "C") (pinfunction "C_C") (pintype "passive"))
      (node (ref "C1") (pin "2") (pinfunction "2_2") (pintype "passive"))
      (node (ref "C15") (pin "1") (pinfunction "1_1") (pintype "passive"))
      (node (ref "C16") (pin "1") (pinfunction "1_1") (pintype "passive"))
      (node (ref "C19") (pin "1") (pinfunction "1_1") (pintype "passive"))
      (node (ref "C2") (pin "1") (pinfunction "1_1") (pintype "passive"))
      (node (ref "C20") (pin "1") (pinfunction "1_1") (pintype "passive"))
      (node (ref "C21") (pin "1") (pinfunction "1_1") (pintype "passive"))
      (node (ref "C26") (pin "1") (pinfunction "1_1") (pintype "passive"))
      (node (ref "C29") (pin "1") (pinfunction "1_1") (pintype "passive"))
      (node (ref "C3") (pin "1") (pinfunction "1_1") (pintype "passive"))
      (node (ref "C32") (pin "2") (pinfunction "2_2") (pintype "passive"))
      (node (ref "C33") (pin "1") (pinfunction "1_1") (pintype "passive"))
      (node (ref "C34") (pin "1") (pinfunction "1_1") (pintype "passive"))
      (node (ref "C35") (pin "2") (pinfunction "2_2") (pintype "passive"))
      (node (ref "C36") (pin "1") (pinfunction "1_1") (pintype "passive"))
      (node (ref "C4") (pin "1") (pinfunction "1_1") (pintype "passive"))
      (node (ref "C6") (pin "1") (pinfunction "1_1") (pintype "passive"))
      (node (ref "C7") (pin "2") (pinfunction "2_2") (pintype "passive"))
      (node (ref "C8") (pin "1") (pinfunction "1_1") (pintype "passive"))
      (node (ref "ENABLE") (pin "1") (pintype "passive"))
      (node (ref "R1") (pin "1") (pinfunction "1_1") (pintype "passive"))
      (node (ref "R4") (pin "1") (pinfunction "1_1") (pintype "passive"))
      (node (ref "R43") (pin "1") (pinfunction "1_1") (pintype "passive"))
      (node (ref "R46") (pin "1") (pinfunction "1_1") (pintype "passive"))
      (node (ref "R50") (pin "2") (pinfunction "2_2") (pintype "passive"))
      (node (ref "R8") (pin "1") (pinfunction "1_1") (pintype "passive"))
      (node (ref "R9") (pin "1") (pinfunction "1_1") (pintype "passive"))
      (node (ref "U1") (pin "0") (pinfunction "EP/GND_0") (pintype "passive"))
      (node (ref "U1") (pin "7") (pinfunction "GND_7") (pintype "passive"))
      (node (ref "U3") (pin "2") (pinfunction "GND_2") (pintype "passive"))
      (node (ref "U4") (pin "4") (pinfunction "GND_4") (pintype "passive"))
      (node (ref "U5") (pin "4") (pinfunction "GND_4") (pintype "passive"))
      (node (ref "U6") (pin "4") (pinfunction "GND_4") (pintype "passive"))
    )
    (net (code "17") (name "Net-(3V3-PadA)") (class "Default")
      (node (ref "3V3") (pin "A") (pinfunction "A_A") (pintype "passive"))
      (node (ref "R55") (pin "2") (pinfunction "2_2") (pintype "passive"))
    )
    (net (code "18") (name "Net-(12V-PadA)") (class "Default")
      (node (ref "12V") (pin "A") (pinfunction "A_A") (pintype "passive"))
      (node (ref "R53") (pin "2") (pinfunction "2_2") (pintype "passive"))
    )
    (net (code "19") (name "Net-(C4-Pad2)") (class "Default")
      (node (ref "C4") (pin "2") (pinfunction "2_2") (pintype "passive"))
      (node (ref "R2") (pin "1") (pinfunction "1_1") (pintype "passive"))
    )
    (net (code "20") (name "Net-(C21-Pad2)") (class "Default")
      (node (ref "C21") (pin "2") (pinfunction "2_2") (pintype "passive"))
      (node (ref "R10") (pin "1") (pinfunction "1_1") (pintype "passive"))
      (node (ref "R11") (pin "1") (pinfunction "1_1") (pintype "passive"))
      (node (ref "R9") (pin "2") (pinfunction "2_2") (pintype "passive"))
    )
    (net (code "21") (name "Net-(C27-Pad1)") (class "Default")
      (node (ref "C27") (pin "1") (pinfunction "1_1") (pintype "passive"))
      (node (ref "R21") (pin "2") (pinfunction "2_2") (pintype "passive"))
      (node (ref "R23") (pin "1") (pinfunction "1_1") (pintype "passive"))
    )
    (net (code "22") (name "Net-(C27-Pad2)") (class "Default")
      (node (ref "C27") (pin "2") (pinfunction "2_2") (pintype "passive"))
      (node (ref "R22") (pin "2") (pinfunction "2_2") (pintype "passive"))
      (node (ref "R24") (pin "1") (pinfunction "1_1") (pintype "passive"))
    )
    (net (code "23") (name "Net-(C28-Pad1)") (class "Default")
      (node (ref "C28") (pin "1") (pinfunction "1_1") (pintype "passive"))
      (node (ref "R27") (pin "1") (pinfunction "1_1") (pintype "passive"))
      (node (ref "R30") (pin "2") (pinfunction "2_2") (pintype "passive"))
    )
    (net (code "24") (name "Net-(C28-Pad2)") (class "Default")
      (node (ref "C28") (pin "2") (pinfunction "2_2") (pintype "passive"))
      (node (ref "R28") (pin "1") (pinfunction "1_1") (pintype "passive"))
      (node (ref "R31") (pin "2") (pinfunction "2_2") (pintype "passive"))
    )
    (net (code "25") (name "Net-(C30-Pad1)") (class "Default")
      (node (ref "C30") (pin "1") (pinfunction "1_1") (pintype "passive"))
      (node (ref "R32") (pin "2") (pinfunction "2_2") (pintype "passive"))
      (node (ref "R35") (pin "1") (pinfunction "1_1") (pintype "passive"))
    )
    (net (code "26") (name "Net-(C30-Pad2)") (class "Default")
      (node (ref "C30") (pin "2") (pinfunction "2_2") (pintype "passive"))
      (node (ref "R33") (pin "2") (pinfunction "2_2") (pintype "passive"))
      (node (ref "R36") (pin "1") (pinfunction "1_1") (pintype "passive"))
    )
    (net (code "27") (name "Net-(C31-Pad1)") (class "Default")
      (node (ref "C31") (pin "1") (pinfunction "1_1") (pintype "passive"))
      (node (ref "R40") (pin "1") (pinfunction "1_1") (pintype "passive"))
      (node (ref "R43") (pin "2") (pinfunction "2_2") (pintype "passive"))
    )
    (net (code "28") (name "Net-(C31-Pad2)") (class "Default")
      (node (ref "C31") (pin "2") (pinfunction "2_2") (pintype "passive"))
      (node (ref "R41") (pin "1") (pinfunction "1_1") (pintype "passive"))
      (node (ref "R44") (pin "2") (pinfunction "2_2") (pintype "passive"))
    )
    (net (code "29") (name "Net-(EN-PadA)") (class "Default")
      (node (ref "EN") (pin "A") (pinfunction "A_A") (pintype "passive"))
      (node (ref "R58") (pin "2") (pinfunction "2_2") (pintype "passive"))
    )
    (net (code "30") (name "Net-(ERR-PadA)") (class "Default")
      (node (ref "ERR") (pin "A") (pinfunction "A_A") (pintype "passive"))
      (node (ref "R56") (pin "2") (pinfunction "2_2") (pintype "passive"))
    )
    (net (code "31") (name "Net-(R57-Pad2)") (class "Default")
      (node (ref "R57") (pin "2") (pinfunction "2_2") (pintype "passive"))
      (node (ref "RUN") (pin "A") (pinfunction "A_A") (pintype "passive"))
    )
    (net (code "32") (name "Net-(U1-BOOT)") (class "Default")
      (node (ref "C5") (pin "1") (pinfunction "1_1") (pintype "passive"))
      (node (ref "U1") (pin "1") (pinfunction "BOOT_1") (pintype "passive"))
    )
    (net (code "33") (name "Net-(U1-COMP)") (class "Default")
      (node (ref "R2") (pin "2") (pinfunction "2_2") (pintype "passive"))
      (node (ref "U1") (pin "6") (pinfunction "COMP_6") (pintype "passive"))
    )
    (net (code "34") (name "Net-(U1-EN)") (class "Default")
      (node (ref "C1") (pin "1") (pinfunction "1_1") (pintype "passive"))
      (node (ref "C2") (pin "2") (pinfunction "2_2") (pintype "passive"))
      (node (ref "C3") (pin "2") (pinfunction "2_2") (pintype "passive"))
      (node (ref "D1") (pin "K") (pinfunction "K_K") (pintype "passive"))
      (node (ref "U1") (pin "2") (pinfunction "VIN_2") (pintype "passive"))
      (node (ref "U1") (pin "3") (pinfunction "EN_3") (pintype "passive"))
    )
    (net (code "35") (name "Net-(U1-FB)") (class "Default")
      (node (ref "R3") (pin "1") (pinfunction "1_1") (pintype "passive"))
      (node (ref "R4") (pin "2") (pinfunction "2_2") (pintype "passive"))
      (node (ref "U1") (pin "5") (pinfunction "FB_5") (pintype "passive"))
    )
    (net (code "36") (name "Net-(U1-RT{slash}CLK)") (class "Default")
      (node (ref "R1") (pin "2") (pinfunction "2_2") (pintype "passive"))
      (node (ref "U1") (pin "4") (pinfunction "RT/CLK_4") (pintype "passive"))
    )
    (net (code "37") (name "Net-(U1-SW)") (class "Default")
      (node (ref "C5") (pin "2") (pinfunction "2_2") (pintype "passive"))
      (node (ref "L1") (pin "1") (pinfunction "1_1") (pintype "passive"))
      (node (ref "U1") (pin "8") (pinfunction "SW_8") (pintype "passive"))
    )
    (net (code "38") (name "Net-(U3-BS)") (class "Default")
      (node (ref "C18") (pin "1") (pinfunction "1_1") (pintype "passive"))
      (node (ref "U3") (pin "1") (pinfunction "BS_1") (pintype "passive"))
    )
    (net (code "39") (name "Net-(U3-FB)") (class "Default")
      (node (ref "C17") (pin "1") (pinfunction "1_1") (pintype "passive"))
      (node (ref "R7") (pin "1") (pinfunction "1_1") (pintype "passive"))
      (node (ref "R8") (pin "2") (pinfunction "2_2") (pintype "passive"))
      (node (ref "U3") (pin "3") (pinfunction "FB_3") (pintype "passive"))
    )
    (net (code "40") (name "Net-(U3-SW)") (class "Default")
      (node (ref "C18") (pin "2") (pinfunction "2_2") (pintype "passive"))
      (node (ref "L3") (pin "2") (pinfunction "2_2") (pintype "passive"))
      (node (ref "U3") (pin "6") (pinfunction "SW_6") (pintype "passive"))
    )
    (net (code "41") (name "Net-(U4-1IN+)") (class "Default")
      (node (ref "R24") (pin "2") (pinfunction "2_2") (pintype "passive"))
      (node (ref "R25") (pin "2") (pinfunction "2_2") (pintype "passive"))
      (node (ref "U4") (pin "3") (pinfunction "1IN+_3") (pintype "passive"))
    )
    (net (code "42") (name "Net-(U4-1IN-)") (class "Default")
      (node (ref "R20") (pin "1") (pinfunction "1_1") (pintype "passive"))
      (node (ref "R23") (pin "2") (pinfunction "2_2") (pintype "passive"))
      (node (ref "U4") (pin "2") (pinfunction "1IN-_2") (pintype "passive"))
    )
    (net (code "43") (name "Net-(U4-2IN+)") (class "Default")
      (node (ref "R28") (pin "2") (pinfunction "2_2") (pintype "passive"))
      (node (ref "R29") (pin "2") (pinfunction "2_2") (pintype "passive"))
      (node (ref "U4") (pin "5") (pinfunction "2IN+_5") (pintype "passive"))
    )
    (net (code "44") (name "Net-(U4-2IN-)") (class "Default")
      (node (ref "R26") (pin "1") (pinfunction "1_1") (pintype "passive"))
      (node (ref "R27") (pin "2") (pinfunction "2_2") (pintype "passive"))
      (node (ref "U4") (pin "6") (pinfunction "2IN-_6") (pintype "passive"))
    )
    (net (code "45") (name "Net-(U5-1IN+)") (class "Default")
      (node (ref "R36") (pin "2") (pinfunction "2_2") (pintype "passive"))
      (node (ref "R37") (pin "2") (pinfunction "2_2") (pintype "passive"))
      (node (ref "U5") (pin "3") (pinfunction "1IN+_3") (pintype "passive"))
    )
    (net (code "46") (name "Net-(U5-1IN-)") (class "Default")
      (node (ref "R34") (pin "1") (pinfunction "1_1") (pintype "passive"))
      (node (ref "R35") (pin "2") (pinfunction "2_2") (pintype "passive"))
      (node (ref "U5") (pin "2") (pinfunction "1IN-_2") (pintype "passive"))
    )
    (net (code "47") (name "Net-(U5-2IN+)") (class "Default")
      (node (ref "R41") (pin "2") (pinfunction "2_2") (pintype "passive"))
      (node (ref "R42") (pin "2") (pinfunction "2_2") (pintype "passive"))
      (node (ref "U5") (pin "5") (pinfunction "2IN+_5") (pintype "passive"))
    )
    (net (code "48") (name "Net-(U5-2IN-)") (class "Default")
      (node (ref "R39") (pin "1") (pinfunction "1_1") (pintype "passive"))
      (node (ref "R40") (pin "2") (pinfunction "2_2") (pintype "passive"))
      (node (ref "U5") (pin "6") (pinfunction "2IN-_6") (pintype "passive"))
    )
    (net (code "49") (name "Net-(U5-2OUT)") (class "Default")
      (node (ref "R38") (pin "1") (pinfunction "1_1") (pintype "passive"))
      (node (ref "R39") (pin "2") (pinfunction "2_2") (pintype "passive"))
      (node (ref "U5") (pin "7") (pinfunction "2OUT_7") (pintype "passive"))
    )
    (net (code "50") (name "Net-(U6-1IN+)") (class "Default")
      (node (ref "R45") (pin "2") (pinfunction "2_2") (pintype "passive"))
      (node (ref "R46") (pin "2") (pinfunction "2_2") (pintype "passive"))
      (node (ref "U6") (pin "3") (pinfunction "1IN+_3") (pintype "passive"))
    )
    (net (code "51") (name "Net-(U6-2IN+)") (class "Default")
      (node (ref "C35") (pin "1") (pinfunction "1_1") (pintype "passive"))
      (node (ref "R51") (pin "1") (pinfunction "1_1") (pintype "passive"))
      (node (ref "U6") (pin "5") (pinfunction "2IN+_5") (pintype "passive"))
    )
    (net (code "52") (name "Net-(U6-2IN-)") (class "Default")
      (node (ref "R49") (pin "1") (pinfunction "1_1") (pintype "passive"))
      (node (ref "R50") (pin "1") (pinfunction "1_1") (pintype "passive"))
      (node (ref "U6") (pin "6") (pinfunction "2IN-_6") (pintype "passive"))
    )
    (net (code "53") (name "Net-(U6-2OUT)") (class "Default")
      (node (ref "R48") (pin "1") (pinfunction "1_1") (pintype "passive"))
      (node (ref "U6") (pin "7") (pinfunction "2OUT_7") (pintype "passive"))
    )
    (net (code "54") (name "VBAT") (class "Default")
      (node (ref "D1") (pin "A") (pinfunction "A_A") (pintype "passive"))
      (node (ref "R10") (pin "2") (pinfunction "2_2") (pintype "passive"))
    )
    (net (code "55") (name "VCC3V3") (class "Default")
      (node (ref "C15") (pin "2") (pinfunction "2_2") (pintype "passive"))
      (node (ref "C16") (pin "2") (pinfunction "2_2") (pintype "passive"))
      (node (ref "C17") (pin "2") (pinfunction "2_2") (pintype "passive"))
      (node (ref "C26") (pin "2") (pinfunction "2_2") (pintype "passive"))
      (node (ref "C29") (pin "2") (pinfunction "2_2") (pintype "passive"))
      (node (ref "C34") (pin "2") (pinfunction "2_2") (pintype "passive"))
      (node (ref "ENABLE") (pin "3") (pintype "passive"))
      (node (ref "L3") (pin "1") (pinfunction "1_1") (pintype "passive"))
      (node (ref "R45") (pin "1") (pinfunction "1_1") (pintype "passive"))
      (node (ref "R47") (pin "1") (pinfunction "1_1") (pintype "passive"))
      (node (ref "R49") (pin "2") (pinfunction "2_2") (pintype "passive"))
      (node (ref "R55") (pin "1") (pinfunction "1_1") (pintype "passive"))
      (node (ref "R56") (pin "1") (pinfunction "1_1") (pintype "passive"))
      (node (ref "R57") (pin "1") (pinfunction "1_1") (pintype "passive"))
      (node (ref "R58") (pin "1") (pinfunction "1_1") (pintype "passive"))
      (node (ref "R7") (pin "2") (pinfunction "2_2") (pintype "passive"))
      (node (ref "U4") (pin "8") (pinfunction "VCC_8") (pintype "passive"))
      (node (ref "U5") (pin "8") (pinfunction "VCC_8") (pintype "passive"))
      (node (ref "U6") (pin "8") (pinfunction "VCC_8") (pintype "passive"))
    )
    (net (code "56") (name "VCC12V") (class "Default")
      (node (ref "C19") (pin "2") (pinfunction "2_2") (pintype "passive"))
      (node (ref "C20") (pin "2") (pinfunction "2_2") (pintype "passive"))
      (node (ref "C6") (pin "2") (pinfunction "2_2") (pintype "passive"))
      (node (ref "C7") (pin "1") (pinfunction "1_1") (pintype "passive"))
      (node (ref "C8") (pin "2") (pinfunction "2_2") (pintype "passive"))
      (node (ref "L1") (pin "2") (pinfunction "2_2") (pintype "passive"))
      (node (ref "R3") (pin "2") (pinfunction "2_2") (pintype "passive"))
      (node (ref "R53") (pin "1") (pinfunction "1_1") (pintype "passive"))
      (node (ref "U3") (pin "4") (pinfunction "EN_4") (pintype "passive"))
      (node (ref "U3") (pin "5") (pinfunction "IN_5") (pintype "passive"))
    )
  )
)
